# analyze_remocon.net
KiCad netlist of a schematic drawn in EAGLE
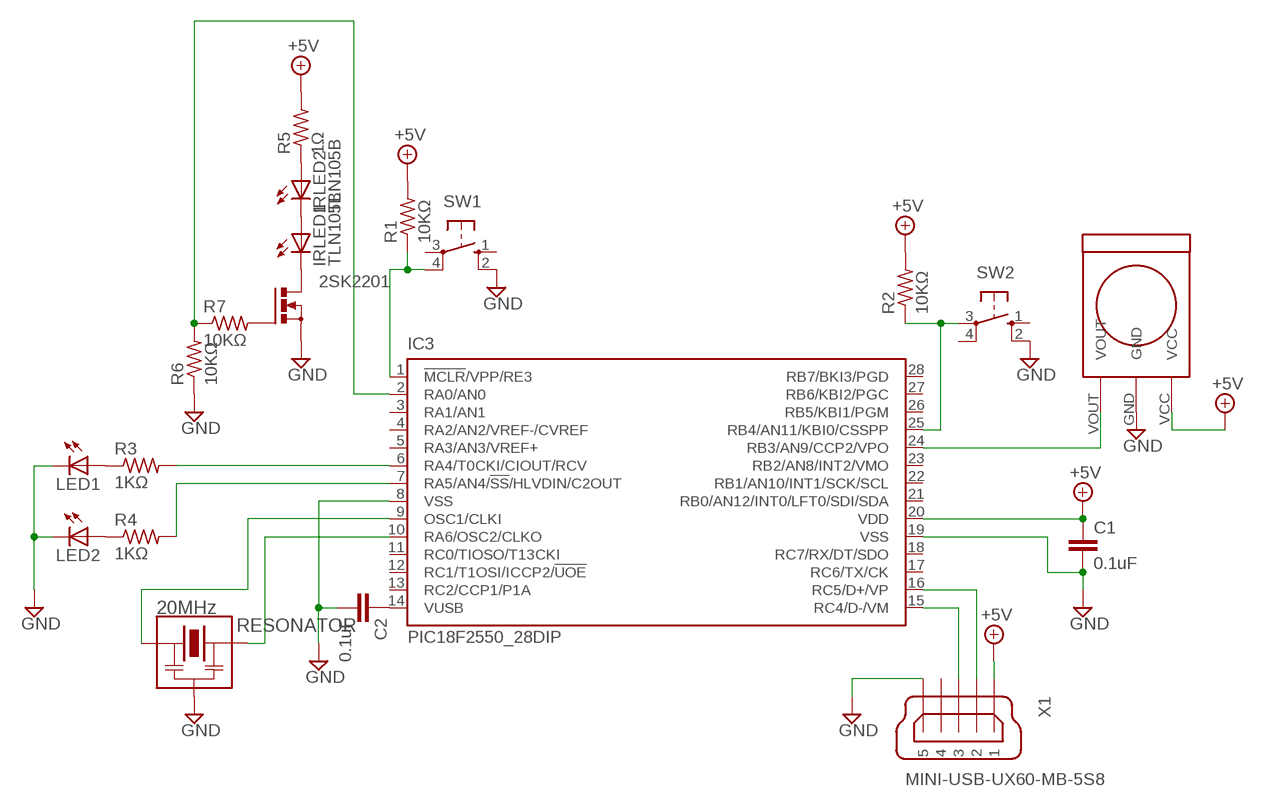
[diagram p0: schematic, sheet 1]

(export (version "E")
  (design (tool "Eeschema 10.0.6"))
  (components
    (comp (ref "2SK2201")
      (value "BUZ11BV")
      (footprint "eagle-import:TO220BV")
      (libsource (lib "eagle-import") (part "BUZ11BV"))
    )
    (comp (ref "C1")
      (value "0.1uF")
      (footprint "eagle-import:C025-024X044")
      (libsource (lib "eagle-import") (part "C-EU025-024X044"))
    )
    (comp (ref "C2")
      (value "0.1uF")
      (footprint "eagle-import:C025-024X044")
      (libsource (lib "eagle-import") (part "C-EU025-024X044"))
    )
    (comp (ref "IC3")
      (value "PIC18F2550_28DIP")
      (footprint "eagle-import:DIL28-3")
      (fields (field (name "MF") "MICROCHIP") (field (name "MPN") "PIC18F2550-I/SP"))
      (libsource (lib "eagle-import") (part "PIC18F2_28DIP550"))
    )
    (comp (ref "IRLED1")
      (value "TLN105B")
      (footprint "eagle-import:LED3MM")
      (libsource (lib "eagle-import") (part "LED3MM"))
    )
    (comp (ref "IRLED2")
      (value "TLN105B")
      (footprint "eagle-import:LED3MM")
      (libsource (lib "eagle-import") (part "LED3MM"))
    )
    (comp (ref "LED1")
      (value "LED3MM")
      (footprint "eagle-import:LED3MM")
      (libsource (lib "eagle-import") (part "LED3MM"))
    )
    (comp (ref "LED2")
      (value "LED3MM")
      (footprint "eagle-import:LED3MM")
      (libsource (lib "eagle-import") (part "LED3MM"))
    )
    (comp (ref "PL-IRM2161-C438")
      (value "IRM2161")
      (footprint "eagle-import:PL-IRM2161-C438")
      (libsource (lib "eagle-import") (part "IRM2161"))
    )
    (comp (ref "R1")
      (value "10KΩ")
      (footprint "eagle-import:MINI_MELF-0102R")
      (libsource (lib "eagle-import") (part "R-US_MELF0102R"))
    )
    (comp (ref "R2")
      (value "10KΩ")
      (footprint "eagle-import:MINI_MELF-0102R")
      (libsource (lib "eagle-import") (part "R-US_MELF0102R"))
    )
    (comp (ref "R3")
      (value "1KΩ")
      (footprint "eagle-import:MINI_MELF-0102R")
      (libsource (lib "eagle-import") (part "R-US_MELF0102R"))
    )
    (comp (ref "R4")
      (value "1KΩ")
      (footprint "eagle-import:MINI_MELF-0102R")
      (libsource (lib "eagle-import") (part "R-US_MELF0102R"))
    )
    (comp (ref "R5")
      (value "1Ω")
      (footprint "eagle-import:0207_7")
      (libsource (lib "eagle-import") (part "R-US_0207/7"))
    )
    (comp (ref "R6")
      (value "10KΩ")
      (footprint "eagle-import:0207_7")
      (libsource (lib "eagle-import") (part "R-US_0207/7"))
    )
    (comp (ref "R7")
      (value "10KΩ")
      (footprint "eagle-import:0207_7")
      (libsource (lib "eagle-import") (part "R-US_0207/7"))
    )
    (comp (ref "RESONATOR")
      (value "20MHz")
      (footprint "eagle-import:HC-49G")
      (libsource (lib "eagle-import") (part "CRES-HA"))
    )
    (comp (ref "SW1")
      (value "10-XX")
      (footprint "eagle-import:B3F-10XX")
      (fields (field (name "MPN") "B3F-1000"))
      (libsource (lib "eagle-import") (part "10-XX"))
    )
    (comp (ref "SW2")
      (value "10-XX")
      (footprint "eagle-import:B3F-10XX")
      (fields (field (name "MPN") "B3F-1000"))
      (libsource (lib "eagle-import") (part "10-XX"))
    )
    (comp (ref "X1")
      (value "MINI-USB-UX60-MB-5S8")
      (footprint "eagle-import:UX60-MB-5S8")
      (libsource (lib "eagle-import") (part "MINI-USB-UX60-MB-5S8"))
    )
  )
  (nets
    (net (code "1") (name "+5V") (class "Default")
      (node (ref "C1") (pin "1") (pinfunction "1_1") (pintype "passive"))
      (node (ref "IC3") (pin "20") (pinfunction "VDD_20") (pintype "power_in"))
      (node (ref "PL-IRM2161-C438") (pin "VCC") (pinfunction "VCC_VCC") (pintype "bidirectional"))
      (node (ref "R1") (pin "2") (pinfunction "2_2") (pintype "passive"))
      (node (ref "R2") (pin "2") (pinfunction "2_2") (pintype "passive"))
      (node (ref "R5") (pin "2") (pinfunction "2_2") (pintype "passive"))
      (node (ref "X1") (pin "1") (pinfunction "1_1") (pintype "input"))
    )
    (net (code "2") (name "GND") (class "Default")
      (node (ref "2SK2201") (pin "S") (pinfunction "S_S") (pintype "passive"))
      (node (ref "C1") (pin "2") (pinfunction "2_2") (pintype "passive"))
      (node (ref "C2") (pin "2") (pinfunction "2_2") (pintype "passive"))
      (node (ref "IC3") (pin "19") (pinfunction "VSS_19") (pintype "power_in"))
      (node (ref "IC3") (pin "8") (pinfunction "VSS_8") (pintype "power_in"))
      (node (ref "LED1") (pin "K") (pinfunction "C_K") (pintype "passive"))
      (node (ref "LED2") (pin "K") (pinfunction "C_K") (pintype "passive"))
      (node (ref "PL-IRM2161-C438") (pin "GND") (pinfunction "GND_GND") (pintype "bidirectional"))
      (node (ref "R6") (pin "1") (pinfunction "1_1") (pintype "passive"))
      (node (ref "RESONATOR") (pin "CENT") (pinfunction "GND_CENT") (pintype "bidirectional"))
      (node (ref "SW1") (pin "2") (pinfunction "S1_2") (pintype "passive"))
      (node (ref "SW2") (pin "2") (pinfunction "S1_2") (pintype "passive"))
      (node (ref "X1") (pin "5") (pinfunction "5_5") (pintype "input"))
    )
    (net (code "3") (name "Net-(2SK2201-PadG)") (class "Default")
      (node (ref "2SK2201") (pin "G") (pinfunction "G_G") (pintype "passive"))
      (node (ref "R7") (pin "2") (pinfunction "2_2") (pintype "passive"))
    )
    (net (code "4") (name "Net-(IC3-OSC1{slash}CLKI)") (class "Default")
      (node (ref "IC3") (pin "9") (pinfunction "OSC1/CLKI_9") (pintype "input"))
      (node (ref "RESONATOR") (pin "P1") (pinfunction "LFT_P1") (pintype "bidirectional"))
    )
    (net (code "5") (name "Net-(IC3-RA0{slash}AN0)") (class "Default")
      (node (ref "IC3") (pin "2") (pinfunction "RA0/AN0_2") (pintype "bidirectional"))
      (node (ref "R6") (pin "2") (pinfunction "2_2") (pintype "passive"))
      (node (ref "R7") (pin "1") (pinfunction "1_1") (pintype "passive"))
    )
    (net (code "6") (name "Net-(IC3-RA4{slash}T0CKI{slash}CIOUT{slash}RCV)") (class "Default")
      (node (ref "IC3") (pin "6") (pinfunction "RA4/T0CKI/CIOUT/RCV_6") (pintype "bidirectional"))
      (node (ref "R3") (pin "2") (pinfunction "2_2") (pintype "passive"))
    )
    (net (code "7") (name "Net-(IC3-RA5{slash}AN4{slash}~{SS}{slash}HLVDIN{slash}C2OUT)") (class "Default")
      (node (ref "IC3") (pin "7") (pinfunction "RA5/AN4/~{SS}/HLVDIN/C2OUT_7") (pintype "bidirectional"))
      (node (ref "R4") (pin "2") (pinfunction "2_2") (pintype "passive"))
    )
    (net (code "8") (name "Net-(IC3-RA6{slash}OSC2{slash}CLKO)") (class "Default")
      (node (ref "IC3") (pin "10") (pinfunction "RA6/OSC2/CLKO_10") (pintype "output"))
      (node (ref "RESONATOR") (pin "P2") (pinfunction "RIT_P2") (pintype "bidirectional"))
    )
    (net (code "9") (name "Net-(IC3-RB3{slash}AN9{slash}CCP2{slash}VPO)") (class "Default")
      (node (ref "IC3") (pin "24") (pinfunction "RB3/AN9/CCP2/VPO_24") (pintype "bidirectional"))
      (node (ref "PL-IRM2161-C438") (pin "VOUT") (pinfunction "VOUT_VOUT") (pintype "bidirectional"))
    )
    (net (code "10") (name "Net-(IC3-RB4{slash}AN11{slash}KBI0{slash}CSSPP)") (class "Default")
      (node (ref "IC3") (pin "25") (pinfunction "RB4/AN11/KBI0/CSSPP_25") (pintype "bidirectional"))
      (node (ref "R2") (pin "1") (pinfunction "1_1") (pintype "passive"))
      (node (ref "SW2") (pin "3") (pinfunction "P_3") (pintype "passive"))
    )
    (net (code "11") (name "Net-(IC3-RC4{slash}D-{slash}VM)") (class "Default")
      (node (ref "IC3") (pin "15") (pinfunction "RC4/D-/VM_15") (pintype "bidirectional"))
      (node (ref "X1") (pin "3") (pinfunction "3_3") (pintype "input"))
    )
    (net (code "12") (name "Net-(IC3-RC5{slash}D+{slash}VP)") (class "Default")
      (node (ref "IC3") (pin "16") (pinfunction "RC5/D+/VP_16") (pintype "bidirectional"))
      (node (ref "X1") (pin "2") (pinfunction "2_2") (pintype "input"))
    )
    (net (code "13") (name "Net-(IC3-VUSB)") (class "Default")
      (node (ref "C2") (pin "1") (pinfunction "1_1") (pintype "passive"))
      (node (ref "IC3") (pin "14") (pinfunction "VUSB_14") (pintype "bidirectional"))
    )
    (net (code "14") (name "Net-(IC3-~{MCLR}{slash}VPP{slash}RE3)") (class "Default")
      (node (ref "IC3") (pin "1") (pinfunction "~{MCLR}/VPP/RE3_1") (pintype "input"))
      (node (ref "R1") (pin "1") (pinfunction "1_1") (pintype "passive"))
      (node (ref "SW1") (pin "4") (pinfunction "P1_4") (pintype "passive"))
    )
    (net (code "15") (name "Net-(IRLED1-C)") (class "Default")
      (node (ref "2SK2201") (pin "D") (pinfunction "D_D") (pintype "passive"))
      (node (ref "IRLED1") (pin "K") (pinfunction "C_K") (pintype "passive"))
    )
    (net (code "16") (name "Net-(IRLED2-C)") (class "Default")
      (node (ref "IRLED1") (pin "A") (pinfunction "A_A") (pintype "passive"))
      (node (ref "IRLED2") (pin "K") (pinfunction "C_K") (pintype "passive"))
    )
    (net (code "17") (name "Net-(IRLED2-PadA)") (class "Default")
      (node (ref "IRLED2") (pin "A") (pinfunction "A_A") (pintype "passive"))
      (node (ref "R5") (pin "1") (pinfunction "1_1") (pintype "passive"))
    )
    (net (code "18") (name "Net-(LED1-PadA)") (class "Default")
      (node (ref "LED1") (pin "A") (pinfunction "A_A") (pintype "passive"))
      (node (ref "R3") (pin "1") (pinfunction "1_1") (pintype "passive"))
    )
    (net (code "19") (name "Net-(LED2-PadA)") (class "Default")
      (node (ref "LED2") (pin "A") (pinfunction "A_A") (pintype "passive"))
      (node (ref "R4") (pin "1") (pinfunction "1_1") (pintype "passive"))
    )
    (net (code "20") (name "unconnected-(IC3-RA1{slash}AN1-Pad3)") (class "Default")
      (node (ref "IC3") (pin "3") (pinfunction "RA1/AN1_3") (pintype "bidirectional"))
    )
    (net (code "21") (name "unconnected-(IC3-RA2{slash}AN2{slash}VREF-{slash}CVREF-Pad4)") (class "Default")
      (node (ref "IC3") (pin "4") (pinfunction "RA2/AN2/VREF-/CVREF_4") (pintype "bidirectional"))
    )
    (net (code "22") (name "unconnected-(IC3-RA3{slash}AN3{slash}VREF+-Pad5)") (class "Default")
      (node (ref "IC3") (pin "5") (pinfunction "RA3/AN3/VREF+_5") (pintype "bidirectional"))
    )
    (net (code "23") (name "unconnected-(IC3-RB0{slash}AN12{slash}INT0{slash}LFT0{slash}SDI{slash}SDA-Pad21)") (class "Default")
      (node (ref "IC3") (pin "21") (pinfunction "RB0/AN12/INT0/LFT0/SDI/SDA_21") (pintype "bidirectional"))
    )
    (net (code "24") (name "unconnected-(IC3-RB1{slash}AN10{slash}INT1{slash}SCK{slash}SCL-Pad22)") (class "Default")
      (node (ref "IC3") (pin "22") (pinfunction "RB1/AN10/INT1/SCK/SCL_22") (pintype "bidirectional"))
    )
    (net (code "25") (name "unconnected-(IC3-RB2{slash}AN8{slash}INT2{slash}VMO-Pad23)") (class "Default")
      (node (ref "IC3") (pin "23") (pinfunction "RB2/AN8/INT2/VMO_23") (pintype "bidirectional"))
    )
    (net (code "26") (name "unconnected-(IC3-RB5{slash}KBI1{slash}PGM-Pad26)") (class "Default")
      (node (ref "IC3") (pin "26") (pinfunction "RB5/KBI1/PGM_26") (pintype "bidirectional"))
    )
    (net (code "27") (name "unconnected-(IC3-RB6{slash}KBI2{slash}PGC-Pad27)") (class "Default")
      (node (ref "IC3") (pin "27") (pinfunction "RB6/KBI2/PGC_27") (pintype "bidirectional"))
    )
    (net (code "28") (name "unconnected-(IC3-RB7{slash}BKI3{slash}PGD-Pad28)") (class "Default")
      (node (ref "IC3") (pin "28") (pinfunction "RB7/BKI3/PGD_28") (pintype "bidirectional"))
    )
    (net (code "29") (name "unconnected-(IC3-RC0{slash}TIOSO{slash}T13CKI-Pad11)") (class "Default")
      (node (ref "IC3") (pin "11") (pinfunction "RC0/TIOSO/T13CKI_11") (pintype "bidirectional"))
    )
    (net (code "30") (name "unconnected-(IC3-RC1{slash}T1OSI{slash}ICCP2{slash}~{UOE}-Pad12)") (class "Default")
      (node (ref "IC3") (pin "12") (pinfunction "RC1/T1OSI/ICCP2/~{UOE}_12") (pintype "bidirectional"))
    )
    (net (code "31") (name "unconnected-(IC3-RC2{slash}CCP1{slash}P1A-Pad13)") (class "Default")
      (node (ref "IC3") (pin "13") (pinfunction "RC2/CCP1/P1A_13") (pintype "bidirectional"))
    )
    (net (code "32") (name "unconnected-(IC3-RC6{slash}TX{slash}CK-Pad17)") (class "Default")
      (node (ref "IC3") (pin "17") (pinfunction "RC6/TX/CK_17") (pintype "bidirectional"))
    )
    (net (code "33") (name "unconnected-(IC3-RC7{slash}RX{slash}DT{slash}SDO-Pad18)") (class "Default")
      (node (ref "IC3") (pin "18") (pinfunction "RC7/RX/DT/SDO_18") (pintype "bidirectional"))
    )
    (net (code "34") (name "unconnected-(SW1-P-Pad3)") (class "Default")
      (node (ref "SW1") (pin "3") (pinfunction "P_3") (pintype "passive"))
    )
    (net (code "35") (name "unconnected-(SW1-S-Pad1)") (class "Default")
      (node (ref "SW1") (pin "1") (pinfunction "S_1") (pintype "passive"))
    )
    (net (code "36") (name "unconnected-(SW2-P1-Pad4)") (class "Default")
      (node (ref "SW2") (pin "4") (pinfunction "P1_4") (pintype "passive"))
    )
    (net (code "37") (name "unconnected-(SW2-S-Pad1)") (class "Default")
      (node (ref "SW2") (pin "1") (pinfunction "S_1") (pintype "passive"))
    )
    (net (code "38") (name "unconnected-(X1-Pad4)") (class "Default")
      (node (ref "X1") (pin "4") (pinfunction "4_4") (pintype "input"))
    )
  )
)
